# VDC.net
KiCad netlist of a schematic drawn in EAGLE
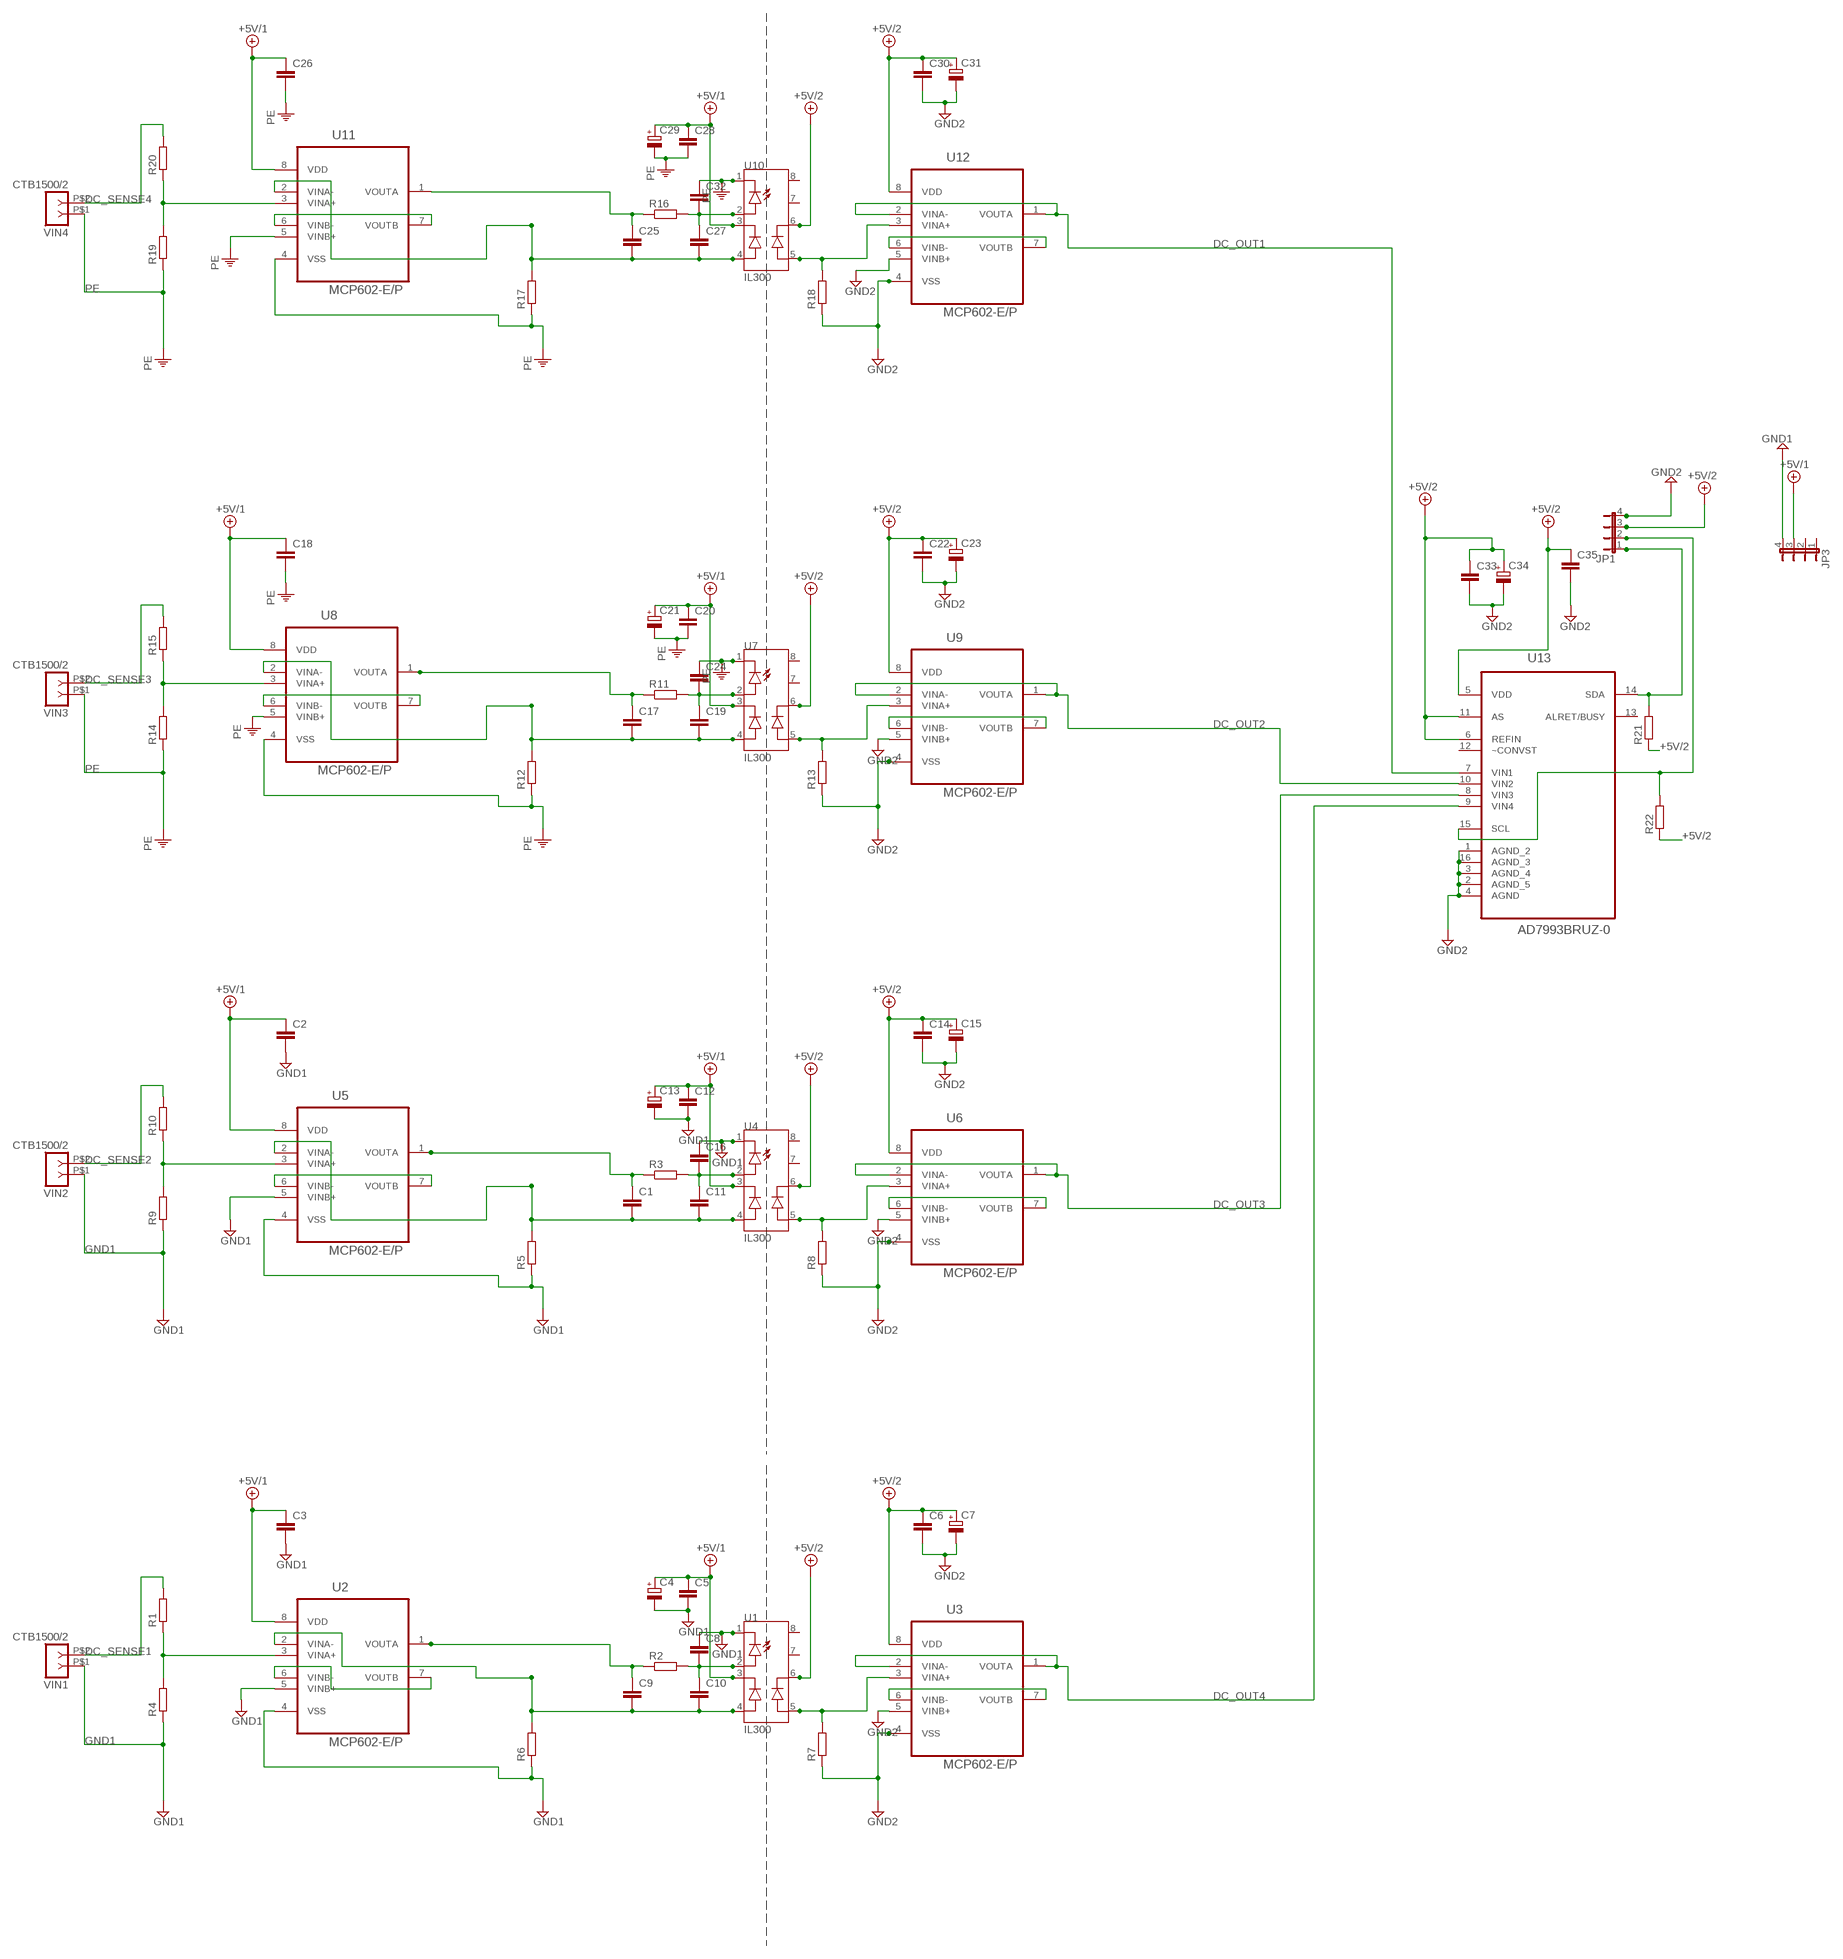
[diagram p0: schematic, sheet 1]

(export (version "E")
  (design (tool "Eeschema 10.0.6"))
  (components
    (comp (ref "C1")
      (value "C-EU025-040X050")
      (footprint "eagle-import:C025-040X050")
      (libsource (lib "eagle-import") (part "C-EU025-040X050"))
    )
    (comp (ref "C2")
      (value "C-EU025-040X050")
      (footprint "eagle-import:C025-040X050")
      (libsource (lib "eagle-import") (part "C-EU025-040X050"))
    )
    (comp (ref "C3")
      (value "C-EU025-040X050")
      (footprint "eagle-import:C025-040X050")
      (libsource (lib "eagle-import") (part "C-EU025-040X050"))
    )
    (comp (ref "C4")
      (value "CPOL-EUE2-5")
      (footprint "eagle-import:E2-5")
      (libsource (lib "eagle-import") (part "CPOL-EUE2-5"))
    )
    (comp (ref "C5")
      (value "C-EU025-040X050")
      (footprint "eagle-import:C025-040X050")
      (libsource (lib "eagle-import") (part "C-EU025-040X050"))
    )
    (comp (ref "C6")
      (value "C-EU025-040X050")
      (footprint "eagle-import:C025-040X050")
      (libsource (lib "eagle-import") (part "C-EU025-040X050"))
    )
    (comp (ref "C7")
      (value "CPOL-EUE2-5")
      (footprint "eagle-import:E2-5")
      (libsource (lib "eagle-import") (part "CPOL-EUE2-5"))
    )
    (comp (ref "C8")
      (value "C-EU025-040X050")
      (footprint "eagle-import:C025-040X050")
      (libsource (lib "eagle-import") (part "C-EU025-040X050"))
    )
    (comp (ref "C9")
      (value "C-EU025-040X050")
      (footprint "eagle-import:C025-040X050")
      (libsource (lib "eagle-import") (part "C-EU025-040X050"))
    )
    (comp (ref "C10")
      (value "C-EU025-040X050")
      (footprint "eagle-import:C025-040X050")
      (libsource (lib "eagle-import") (part "C-EU025-040X050"))
    )
    (comp (ref "C11")
      (value "C-EU025-040X050")
      (footprint "eagle-import:C025-040X050")
      (libsource (lib "eagle-import") (part "C-EU025-040X050"))
    )
    (comp (ref "C12")
      (value "C-EU025-040X050")
      (footprint "eagle-import:C025-040X050")
      (libsource (lib "eagle-import") (part "C-EU025-040X050"))
    )
    (comp (ref "C13")
      (value "CPOL-EUE2-5")
      (footprint "eagle-import:E2-5")
      (libsource (lib "eagle-import") (part "CPOL-EUE2-5"))
    )
    (comp (ref "C14")
      (value "C-EU025-040X050")
      (footprint "eagle-import:C025-040X050")
      (libsource (lib "eagle-import") (part "C-EU025-040X050"))
    )
    (comp (ref "C15")
      (value "CPOL-EUE2-5")
      (footprint "eagle-import:E2-5")
      (libsource (lib "eagle-import") (part "CPOL-EUE2-5"))
    )
    (comp (ref "C16")
      (value "C-EU025-040X050")
      (footprint "eagle-import:C025-040X050")
      (libsource (lib "eagle-import") (part "C-EU025-040X050"))
    )
    (comp (ref "C17")
      (value "C-EU025-040X050")
      (footprint "eagle-import:C025-040X050")
      (libsource (lib "eagle-import") (part "C-EU025-040X050"))
    )
    (comp (ref "C18")
      (value "C-EU025-040X050")
      (footprint "eagle-import:C025-040X050")
      (libsource (lib "eagle-import") (part "C-EU025-040X050"))
    )
    (comp (ref "C19")
      (value "C-EU025-040X050")
      (footprint "eagle-import:C025-040X050")
      (libsource (lib "eagle-import") (part "C-EU025-040X050"))
    )
    (comp (ref "C20")
      (value "C-EU025-040X050")
      (footprint "eagle-import:C025-040X050")
      (libsource (lib "eagle-import") (part "C-EU025-040X050"))
    )
    (comp (ref "C21")
      (value "CPOL-EUE2-5")
      (footprint "eagle-import:E2-5")
      (libsource (lib "eagle-import") (part "CPOL-EUE2-5"))
    )
    (comp (ref "C22")
      (value "C-EU025-040X050")
      (footprint "eagle-import:C025-040X050")
      (libsource (lib "eagle-import") (part "C-EU025-040X050"))
    )
    (comp (ref "C23")
      (value "CPOL-EUE2-5")
      (footprint "eagle-import:E2-5")
      (libsource (lib "eagle-import") (part "CPOL-EUE2-5"))
    )
    (comp (ref "C24")
      (value "C-EU025-040X050")
      (footprint "eagle-import:C025-040X050")
      (libsource (lib "eagle-import") (part "C-EU025-040X050"))
    )
    (comp (ref "C25")
      (value "C-EU025-040X050")
      (footprint "eagle-import:C025-040X050")
      (libsource (lib "eagle-import") (part "C-EU025-040X050"))
    )
    (comp (ref "C26")
      (value "C-EU025-040X050")
      (footprint "eagle-import:C025-040X050")
      (libsource (lib "eagle-import") (part "C-EU025-040X050"))
    )
    (comp (ref "C27")
      (value "C-EU025-040X050")
      (footprint "eagle-import:C025-040X050")
      (libsource (lib "eagle-import") (part "C-EU025-040X050"))
    )
    (comp (ref "C28")
      (value "C-EU025-040X050")
      (footprint "eagle-import:C025-040X050")
      (libsource (lib "eagle-import") (part "C-EU025-040X050"))
    )
    (comp (ref "C29")
      (value "CPOL-EUE2-5")
      (footprint "eagle-import:E2-5")
      (libsource (lib "eagle-import") (part "CPOL-EUE2-5"))
    )
    (comp (ref "C30")
      (value "C-EU025-040X050")
      (footprint "eagle-import:C025-040X050")
      (libsource (lib "eagle-import") (part "C-EU025-040X050"))
    )
    (comp (ref "C31")
      (value "CPOL-EUE2-5")
      (footprint "eagle-import:E2-5")
      (libsource (lib "eagle-import") (part "CPOL-EUE2-5"))
    )
    (comp (ref "C32")
      (value "C-EU025-040X050")
      (footprint "eagle-import:C025-040X050")
      (libsource (lib "eagle-import") (part "C-EU025-040X050"))
    )
    (comp (ref "C33")
      (value "C-EU025-024X044")
      (footprint "eagle-import:C025-024X044")
      (libsource (lib "eagle-import") (part "C-EU025-024X044"))
    )
    (comp (ref "C34")
      (value "CPOL-EUE2-4")
      (footprint "eagle-import:E2-4")
      (libsource (lib "eagle-import") (part "CPOL-EUE2-4"))
    )
    (comp (ref "C35")
      (value "C-EU025-025X050")
      (footprint "eagle-import:C025-025X050")
      (libsource (lib "eagle-import") (part "C-EU025-025X050"))
    )
    (comp (ref "JP1")
      (value "JP4E")
      (footprint "eagle-import:JP4")
      (libsource (lib "eagle-import") (part "JP4E"))
    )
    (comp (ref "JP3")
      (value "JP4E")
      (footprint "eagle-import:JP4")
      (libsource (lib "eagle-import") (part "JP4E"))
    )
    (comp (ref "R1")
      (value "R-EU_0207/10")
      (footprint "eagle-import:0207_10")
      (libsource (lib "eagle-import") (part "R-EU_0207/10"))
    )
    (comp (ref "R2")
      (value "R-EU_0207/10")
      (footprint "eagle-import:0207_10")
      (libsource (lib "eagle-import") (part "R-EU_0207/10"))
    )
    (comp (ref "R3")
      (value "R-EU_0207/10")
      (footprint "eagle-import:0207_10")
      (libsource (lib "eagle-import") (part "R-EU_0207/10"))
    )
    (comp (ref "R4")
      (value "R-EU_0207/10")
      (footprint "eagle-import:0207_10")
      (libsource (lib "eagle-import") (part "R-EU_0207/10"))
    )
    (comp (ref "R5")
      (value "R-EU_0207/10")
      (footprint "eagle-import:0207_10")
      (libsource (lib "eagle-import") (part "R-EU_0207/10"))
    )
    (comp (ref "R6")
      (value "R-EU_0207/10")
      (footprint "eagle-import:0207_10")
      (libsource (lib "eagle-import") (part "R-EU_0207/10"))
    )
    (comp (ref "R7")
      (value "R-EU_0207/10")
      (footprint "eagle-import:0207_10")
      (libsource (lib "eagle-import") (part "R-EU_0207/10"))
    )
    (comp (ref "R8")
      (value "R-EU_0207/10")
      (footprint "eagle-import:0207_10")
      (libsource (lib "eagle-import") (part "R-EU_0207/10"))
    )
    (comp (ref "R9")
      (value "R-EU_0207/10")
      (footprint "eagle-import:0207_10")
      (libsource (lib "eagle-import") (part "R-EU_0207/10"))
    )
    (comp (ref "R10")
      (value "R-EU_0207/10")
      (footprint "eagle-import:0207_10")
      (libsource (lib "eagle-import") (part "R-EU_0207/10"))
    )
    (comp (ref "R11")
      (value "R-EU_0207/10")
      (footprint "eagle-import:0207_10")
      (libsource (lib "eagle-import") (part "R-EU_0207/10"))
    )
    (comp (ref "R12")
      (value "R-EU_0207/10")
      (footprint "eagle-import:0207_10")
      (libsource (lib "eagle-import") (part "R-EU_0207/10"))
    )
    (comp (ref "R13")
      (value "R-EU_0207/10")
      (footprint "eagle-import:0207_10")
      (libsource (lib "eagle-import") (part "R-EU_0207/10"))
    )
    (comp (ref "R14")
      (value "R-EU_0207/10")
      (footprint "eagle-import:0207_10")
      (libsource (lib "eagle-import") (part "R-EU_0207/10"))
    )
    (comp (ref "R15")
      (value "R-EU_0207/10")
      (footprint "eagle-import:0207_10")
      (libsource (lib "eagle-import") (part "R-EU_0207/10"))
    )
    (comp (ref "R16")
      (value "R-EU_0207/10")
      (footprint "eagle-import:0207_10")
      (libsource (lib "eagle-import") (part "R-EU_0207/10"))
    )
    (comp (ref "R17")
      (value "R-EU_0207/10")
      (footprint "eagle-import:0207_10")
      (libsource (lib "eagle-import") (part "R-EU_0207/10"))
    )
    (comp (ref "R18")
      (value "R-EU_0207/10")
      (footprint "eagle-import:0207_10")
      (libsource (lib "eagle-import") (part "R-EU_0207/10"))
    )
    (comp (ref "R19")
      (value "R-EU_0207/10")
      (footprint "eagle-import:0207_10")
      (libsource (lib "eagle-import") (part "R-EU_0207/10"))
    )
    (comp (ref "R20")
      (value "R-EU_0207/10")
      (footprint "eagle-import:0207_10")
      (libsource (lib "eagle-import") (part "R-EU_0207/10"))
    )
    (comp (ref "R21")
      (value "R-EU_0207/10")
      (footprint "eagle-import:0207_10")
      (libsource (lib "eagle-import") (part "R-EU_0207/10"))
    )
    (comp (ref "R22")
      (value "R-EU_0207/10")
      (footprint "eagle-import:0207_10")
      (libsource (lib "eagle-import") (part "R-EU_0207/10"))
    )
    (comp (ref "U1")
      (value "IL300")
      (footprint "eagle-import:DIL08")
      (libsource (lib "eagle-import") (part "IL300"))
    )
    (comp (ref "U2")
      (value "MCP602-E/P")
      (footprint "eagle-import:DIP254P762X508-8P")
      (libsource (lib "eagle-import") (part "MCP602-E/P"))
    )
    (comp (ref "U3")
      (value "MCP602-E/P")
      (footprint "eagle-import:DIP254P762X508-8P")
      (libsource (lib "eagle-import") (part "MCP602-E/P"))
    )
    (comp (ref "U4")
      (value "IL300")
      (footprint "eagle-import:DIL08")
      (libsource (lib "eagle-import") (part "IL300"))
    )
    (comp (ref "U5")
      (value "MCP602-E/P")
      (footprint "eagle-import:DIP254P762X508-8P")
      (libsource (lib "eagle-import") (part "MCP602-E/P"))
    )
    (comp (ref "U6")
      (value "MCP602-E/P")
      (footprint "eagle-import:DIP254P762X508-8P")
      (libsource (lib "eagle-import") (part "MCP602-E/P"))
    )
    (comp (ref "U7")
      (value "IL300")
      (footprint "eagle-import:DIL08")
      (libsource (lib "eagle-import") (part "IL300"))
    )
    (comp (ref "U8")
      (value "MCP602-E/P")
      (footprint "eagle-import:DIP254P762X508-8P")
      (libsource (lib "eagle-import") (part "MCP602-E/P"))
    )
    (comp (ref "U9")
      (value "MCP602-E/P")
      (footprint "eagle-import:DIP254P762X508-8P")
      (libsource (lib "eagle-import") (part "MCP602-E/P"))
    )
    (comp (ref "U10")
      (value "IL300")
      (footprint "eagle-import:DIL08")
      (libsource (lib "eagle-import") (part "IL300"))
    )
    (comp (ref "U11")
      (value "MCP602-E/P")
      (footprint "eagle-import:DIP254P762X508-8P")
      (libsource (lib "eagle-import") (part "MCP602-E/P"))
    )
    (comp (ref "U12")
      (value "MCP602-E/P")
      (footprint "eagle-import:DIP254P762X508-8P")
      (libsource (lib "eagle-import") (part "MCP602-E/P"))
    )
    (comp (ref "U13")
      (value "AD7993BRUZ-0")
      (footprint "eagle-import:SOP65P640X120-16N")
      (libsource (lib "eagle-import") (part "AD7993BRUZ-0"))
    )
    (comp (ref "VIN1")
      (value "CTB1500/2")
      (footprint "eagle-import:CTB1500-2")
      (libsource (lib "eagle-import") (part "CTB1500/2"))
    )
    (comp (ref "VIN2")
      (value "CTB1500/2")
      (footprint "eagle-import:CTB1500-2")
      (libsource (lib "eagle-import") (part "CTB1500/2"))
    )
    (comp (ref "VIN3")
      (value "CTB1500/2")
      (footprint "eagle-import:CTB1500-2")
      (libsource (lib "eagle-import") (part "CTB1500/2"))
    )
    (comp (ref "VIN4")
      (value "CTB1500/2")
      (footprint "eagle-import:CTB1500-2")
      (libsource (lib "eagle-import") (part "CTB1500/2"))
    )
  )
  (nets
    (net (code "1") (name "+5V{slash}1") (class "Default")
      (node (ref "C12") (pin "1") (pinfunction "1_1") (pintype "passive"))
      (node (ref "C13") (pin "+") (pinfunction "+_+") (pintype "passive"))
      (node (ref "C18") (pin "1") (pinfunction "1_1") (pintype "passive"))
      (node (ref "C2") (pin "1") (pinfunction "1_1") (pintype "passive"))
      (node (ref "C20") (pin "1") (pinfunction "1_1") (pintype "passive"))
      (node (ref "C21") (pin "+") (pinfunction "+_+") (pintype "passive"))
      (node (ref "C26") (pin "1") (pinfunction "1_1") (pintype "passive"))
      (node (ref "C28") (pin "1") (pinfunction "1_1") (pintype "passive"))
      (node (ref "C29") (pin "+") (pinfunction "+_+") (pintype "passive"))
      (node (ref "C3") (pin "1") (pinfunction "1_1") (pintype "passive"))
      (node (ref "C4") (pin "+") (pinfunction "+_+") (pintype "passive"))
      (node (ref "C5") (pin "1") (pinfunction "1_1") (pintype "passive"))
      (node (ref "JP3") (pin "3") (pinfunction "3_3") (pintype "passive"))
      (node (ref "U1") (pin "3") (pinfunction "C_FB_3") (pintype "passive"))
      (node (ref "U10") (pin "3") (pinfunction "C_FB_3") (pintype "passive"))
      (node (ref "U11") (pin "8") (pinfunction "VDD_8") (pintype "power_in"))
      (node (ref "U2") (pin "8") (pinfunction "VDD_8") (pintype "power_in"))
      (node (ref "U4") (pin "3") (pinfunction "C_FB_3") (pintype "passive"))
      (node (ref "U5") (pin "8") (pinfunction "VDD_8") (pintype "power_in"))
      (node (ref "U7") (pin "3") (pinfunction "C_FB_3") (pintype "passive"))
      (node (ref "U8") (pin "8") (pinfunction "VDD_8") (pintype "power_in"))
    )
    (net (code "2") (name "+5V{slash}2") (class "Default")
      (node (ref "C14") (pin "1") (pinfunction "1_1") (pintype "passive"))
      (node (ref "C15") (pin "+") (pinfunction "+_+") (pintype "passive"))
      (node (ref "C22") (pin "1") (pinfunction "1_1") (pintype "passive"))
      (node (ref "C23") (pin "+") (pinfunction "+_+") (pintype "passive"))
      (node (ref "C30") (pin "1") (pinfunction "1_1") (pintype "passive"))
      (node (ref "C31") (pin "+") (pinfunction "+_+") (pintype "passive"))
      (node (ref "C33") (pin "1") (pinfunction "1_1") (pintype "passive"))
      (node (ref "C34") (pin "+") (pinfunction "+_+") (pintype "passive"))
      (node (ref "C35") (pin "1") (pinfunction "1_1") (pintype "passive"))
      (node (ref "C6") (pin "1") (pinfunction "1_1") (pintype "passive"))
      (node (ref "C7") (pin "+") (pinfunction "+_+") (pintype "passive"))
      (node (ref "JP1") (pin "3") (pinfunction "3_3") (pintype "passive"))
      (node (ref "R21") (pin "1") (pinfunction "1_1") (pintype "passive"))
      (node (ref "R22") (pin "1") (pinfunction "1_1") (pintype "passive"))
      (node (ref "U1") (pin "6") (pinfunction "C_OUT_6") (pintype "passive"))
      (node (ref "U10") (pin "6") (pinfunction "C_OUT_6") (pintype "passive"))
      (node (ref "U12") (pin "8") (pinfunction "VDD_8") (pintype "power_in"))
      (node (ref "U13") (pin "11") (pinfunction "AS_11") (pintype "input"))
      (node (ref "U13") (pin "5") (pinfunction "VDD_5") (pintype "power_in"))
      (node (ref "U13") (pin "6") (pinfunction "REFIN_6") (pintype "input"))
      (node (ref "U3") (pin "8") (pinfunction "VDD_8") (pintype "power_in"))
      (node (ref "U4") (pin "6") (pinfunction "C_OUT_6") (pintype "passive"))
      (node (ref "U6") (pin "8") (pinfunction "VDD_8") (pintype "power_in"))
      (node (ref "U7") (pin "6") (pinfunction "C_OUT_6") (pintype "passive"))
      (node (ref "U9") (pin "8") (pinfunction "VDD_8") (pintype "power_in"))
    )
    (net (code "3") (name "/DC_OUT1") (class "Default")
      (node (ref "U12") (pin "1") (pinfunction "VOUTA_1") (pintype "output"))
      (node (ref "U12") (pin "2") (pinfunction "VINA-_2") (pintype "input"))
      (node (ref "U13") (pin "7") (pinfunction "VIN1_7") (pintype "input"))
    )
    (net (code "4") (name "/DC_OUT2") (class "Default")
      (node (ref "U13") (pin "10") (pinfunction "VIN2_10") (pintype "input"))
      (node (ref "U9") (pin "1") (pinfunction "VOUTA_1") (pintype "output"))
      (node (ref "U9") (pin "2") (pinfunction "VINA-_2") (pintype "input"))
    )
    (net (code "5") (name "/DC_OUT3") (class "Default")
      (node (ref "U13") (pin "8") (pinfunction "VIN3_8") (pintype "input"))
      (node (ref "U6") (pin "1") (pinfunction "VOUTA_1") (pintype "output"))
      (node (ref "U6") (pin "2") (pinfunction "VINA-_2") (pintype "input"))
    )
    (net (code "6") (name "/DC_OUT4") (class "Default")
      (node (ref "U13") (pin "9") (pinfunction "VIN4_9") (pintype "input"))
      (node (ref "U3") (pin "1") (pinfunction "VOUTA_1") (pintype "output"))
      (node (ref "U3") (pin "2") (pinfunction "VINA-_2") (pintype "input"))
    )
    (net (code "7") (name "/DC_SENSE1") (class "Default")
      (node (ref "R1") (pin "2") (pinfunction "2_2") (pintype "passive"))
      (node (ref "VIN1") (pin "P$2") (pinfunction "2_P$2") (pintype "passive"))
    )
    (net (code "8") (name "/DC_SENSE2") (class "Default")
      (node (ref "R10") (pin "2") (pinfunction "2_2") (pintype "passive"))
      (node (ref "VIN2") (pin "P$2") (pinfunction "2_P$2") (pintype "passive"))
    )
    (net (code "9") (name "/DC_SENSE3") (class "Default")
      (node (ref "R15") (pin "2") (pinfunction "2_2") (pintype "passive"))
      (node (ref "VIN3") (pin "P$2") (pinfunction "2_P$2") (pintype "passive"))
    )
    (net (code "10") (name "/DC_SENSE4") (class "Default")
      (node (ref "R20") (pin "2") (pinfunction "2_2") (pintype "passive"))
      (node (ref "VIN4") (pin "P$2") (pinfunction "2_P$2") (pintype "passive"))
    )
    (net (code "11") (name "GND1") (class "Default")
      (node (ref "C12") (pin "2") (pinfunction "2_2") (pintype "passive"))
      (node (ref "C13") (pin "-") (pinfunction "-_-") (pintype "passive"))
      (node (ref "C16") (pin "1") (pinfunction "1_1") (pintype "passive"))
      (node (ref "C2") (pin "2") (pinfunction "2_2") (pintype "passive"))
      (node (ref "C3") (pin "2") (pinfunction "2_2") (pintype "passive"))
      (node (ref "C4") (pin "-") (pinfunction "-_-") (pintype "passive"))
      (node (ref "C5") (pin "2") (pinfunction "2_2") (pintype "passive"))
      (node (ref "C8") (pin "1") (pinfunction "1_1") (pintype "passive"))
      (node (ref "JP3") (pin "4") (pinfunction "4_4") (pintype "passive"))
      (node (ref "R4") (pin "1") (pinfunction "1_1") (pintype "passive"))
      (node (ref "R5") (pin "1") (pinfunction "1_1") (pintype "passive"))
      (node (ref "R6") (pin "1") (pinfunction "1_1") (pintype "passive"))
      (node (ref "R9") (pin "1") (pinfunction "1_1") (pintype "passive"))
      (node (ref "U1") (pin "1") (pinfunction "C_LED_1") (pintype "passive"))
      (node (ref "U2") (pin "4") (pinfunction "VSS_4") (pintype "power_in"))
      (node (ref "U2") (pin "5") (pinfunction "VINB+_5") (pintype "input"))
      (node (ref "U4") (pin "1") (pinfunction "C_LED_1") (pintype "passive"))
      (node (ref "U5") (pin "4") (pinfunction "VSS_4") (pintype "power_in"))
      (node (ref "U5") (pin "5") (pinfunction "VINB+_5") (pintype "input"))
      (node (ref "VIN1") (pin "P$1") (pinfunction "1_P$1") (pintype "passive"))
      (node (ref "VIN2") (pin "P$1") (pinfunction "1_P$1") (pintype "passive"))
    )
    (net (code "12") (name "GND2") (class "Default")
      (node (ref "C14") (pin "2") (pinfunction "2_2") (pintype "passive"))
      (node (ref "C15") (pin "-") (pinfunction "-_-") (pintype "passive"))
      (node (ref "C22") (pin "2") (pinfunction "2_2") (pintype "passive"))
      (node (ref "C23") (pin "-") (pinfunction "-_-") (pintype "passive"))
      (node (ref "C30") (pin "2") (pinfunction "2_2") (pintype "passive"))
      (node (ref "C31") (pin "-") (pinfunction "-_-") (pintype "passive"))
      (node (ref "C33") (pin "2") (pinfunction "2_2") (pintype "passive"))
      (node (ref "C34") (pin "-") (pinfunction "-_-") (pintype "passive"))
      (node (ref "C35") (pin "2") (pinfunction "2_2") (pintype "passive"))
      (node (ref "C6") (pin "2") (pinfunction "2_2") (pintype "passive"))
      (node (ref "C7") (pin "-") (pinfunction "-_-") (pintype "passive"))
      (node (ref "JP1") (pin "4") (pinfunction "4_4") (pintype "passive"))
      (node (ref "R13") (pin "1") (pinfunction "1_1") (pintype "passive"))
      (node (ref "R18") (pin "1") (pinfunction "1_1") (pintype "passive"))
      (node (ref "R7") (pin "1") (pinfunction "1_1") (pintype "passive"))
      (node (ref "R8") (pin "1") (pinfunction "1_1") (pintype "passive"))
      (node (ref "U12") (pin "4") (pinfunction "VSS_4") (pintype "power_in"))
      (node (ref "U12") (pin "5") (pinfunction "VINB+_5") (pintype "input"))
      (node (ref "U13") (pin "1") (pinfunction "AGND_2_1") (pintype "passive"))
      (node (ref "U13") (pin "16") (pinfunction "AGND_3_16") (pintype "passive"))
      (node (ref "U13") (pin "2") (pinfunction "AGND_5_2") (pintype "passive"))
      (node (ref "U13") (pin "3") (pinfunction "AGND_4_3") (pintype "passive"))
      (node (ref "U13") (pin "4") (pinfunction "AGND_4") (pintype "passive"))
      (node (ref "U3") (pin "4") (pinfunction "VSS_4") (pintype "power_in"))
      (node (ref "U3") (pin "5") (pinfunction "VINB+_5") (pintype "input"))
      (node (ref "U6") (pin "4") (pinfunction "VSS_4") (pintype "power_in"))
      (node (ref "U6") (pin "5") (pinfunction "VINB+_5") (pintype "input"))
      (node (ref "U9") (pin "4") (pinfunction "VSS_4") (pintype "power_in"))
      (node (ref "U9") (pin "5") (pinfunction "VINB+_5") (pintype "input"))
    )
    (net (code "13") (name "Net-(U1-A_FB)") (class "Default")
      (node (ref "C10") (pin "2") (pinfunction "2_2") (pintype "passive"))
      (node (ref "C9") (pin "2") (pinfunction "2_2") (pintype "passive"))
      (node (ref "R6") (pin "2") (pinfunction "2_2") (pintype "passive"))
      (node (ref "U1") (pin "4") (pinfunction "A_FB_4") (pintype "passive"))
      (node (ref "U2") (pin "2") (pinfunction "VINA-_2") (pintype "input"))
    )
    (net (code "14") (name "Net-(U1-A_LED)") (class "Default")
      (node (ref "C10") (pin "1") (pinfunction "1_1") (pintype "passive"))
      (node (ref "C8") (pin "2") (pinfunction "2_2") (pintype "passive"))
      (node (ref "R2") (pin "2") (pinfunction "2_2") (pintype "passive"))
      (node (ref "U1") (pin "2") (pinfunction "A_LED_2") (pintype "passive"))
    )
    (net (code "15") (name "Net-(U1-A_OUT)") (class "Default")
      (node (ref "R7") (pin "2") (pinfunction "2_2") (pintype "passive"))
      (node (ref "U1") (pin "5") (pinfunction "A_OUT_5") (pintype "passive"))
      (node (ref "U3") (pin "3") (pinfunction "VINA+_3") (pintype "input"))
    )
    (net (code "16") (name "Net-(U2-VINA+)") (class "Default")
      (node (ref "R1") (pin "1") (pinfunction "1_1") (pintype "passive"))
      (node (ref "R4") (pin "2") (pinfunction "2_2") (pintype "passive"))
      (node (ref "U2") (pin "3") (pinfunction "VINA+_3") (pintype "input"))
    )
    (net (code "17") (name "Net-(U2-VINB-)") (class "Default")
      (node (ref "U2") (pin "6") (pinfunction "VINB-_6") (pintype "input"))
      (node (ref "U2") (pin "7") (pinfunction "VOUTB_7") (pintype "output"))
    )
    (net (code "18") (name "Net-(U2-VOUTA)") (class "Default")
      (node (ref "C9") (pin "1") (pinfunction "1_1") (pintype "passive"))
      (node (ref "R2") (pin "1") (pinfunction "1_1") (pintype "passive"))
      (node (ref "U2") (pin "1") (pinfunction "VOUTA_1") (pintype "output"))
    )
    (net (code "19") (name "Net-(U3-VINB-)") (class "Default")
      (node (ref "U3") (pin "6") (pinfunction "VINB-_6") (pintype "input"))
      (node (ref "U3") (pin "7") (pinfunction "VOUTB_7") (pintype "output"))
    )
    (net (code "20") (name "Net-(U4-A_FB)") (class "Default")
      (node (ref "C1") (pin "2") (pinfunction "2_2") (pintype "passive"))
      (node (ref "C11") (pin "2") (pinfunction "2_2") (pintype "passive"))
      (node (ref "R5") (pin "2") (pinfunction "2_2") (pintype "passive"))
      (node (ref "U4") (pin "4") (pinfunction "A_FB_4") (pintype "passive"))
      (node (ref "U5") (pin "2") (pinfunction "VINA-_2") (pintype "input"))
    )
    (net (code "21") (name "Net-(U4-A_LED)") (class "Default")
      (node (ref "C11") (pin "1") (pinfunction "1_1") (pintype "passive"))
      (node (ref "C16") (pin "2") (pinfunction "2_2") (pintype "passive"))
      (node (ref "R3") (pin "2") (pinfunction "2_2") (pintype "passive"))
      (node (ref "U4") (pin "2") (pinfunction "A_LED_2") (pintype "passive"))
    )
    (net (code "22") (name "Net-(U4-A_OUT)") (class "Default")
      (node (ref "R8") (pin "2") (pinfunction "2_2") (pintype "passive"))
      (node (ref "U4") (pin "5") (pinfunction "A_OUT_5") (pintype "passive"))
      (node (ref "U6") (pin "3") (pinfunction "VINA+_3") (pintype "input"))
    )
    (net (code "23") (name "Net-(U5-VINA+)") (class "Default")
      (node (ref "R10") (pin "1") (pinfunction "1_1") (pintype "passive"))
      (node (ref "R9") (pin "2") (pinfunction "2_2") (pintype "passive"))
      (node (ref "U5") (pin "3") (pinfunction "VINA+_3") (pintype "input"))
    )
    (net (code "24") (name "Net-(U5-VINB-)") (class "Default")
      (node (ref "U5") (pin "6") (pinfunction "VINB-_6") (pintype "input"))
      (node (ref "U5") (pin "7") (pinfunction "VOUTB_7") (pintype "output"))
    )
    (net (code "25") (name "Net-(U5-VOUTA)") (class "Default")
      (node (ref "C1") (pin "1") (pinfunction "1_1") (pintype "passive"))
      (node (ref "R3") (pin "1") (pinfunction "1_1") (pintype "passive"))
      (node (ref "U5") (pin "1") (pinfunction "VOUTA_1") (pintype "output"))
    )
    (net (code "26") (name "Net-(U6-VINB-)") (class "Default")
      (node (ref "U6") (pin "6") (pinfunction "VINB-_6") (pintype "input"))
      (node (ref "U6") (pin "7") (pinfunction "VOUTB_7") (pintype "output"))
    )
    (net (code "27") (name "Net-(U7-A_FB)") (class "Default")
      (node (ref "C17") (pin "2") (pinfunction "2_2") (pintype "passive"))
      (node (ref "C19") (pin "2") (pinfunction "2_2") (pintype "passive"))
      (node (ref "R12") (pin "2") (pinfunction "2_2") (pintype "passive"))
      (node (ref "U7") (pin "4") (pinfunction "A_FB_4") (pintype "passive"))
      (node (ref "U8") (pin "2") (pinfunction "VINA-_2") (pintype "input"))
    )
    (net (code "28") (name "Net-(U7-A_LED)") (class "Default")
      (node (ref "C19") (pin "1") (pinfunction "1_1") (pintype "passive"))
      (node (ref "C24") (pin "2") (pinfunction "2_2") (pintype "passive"))
      (node (ref "R11") (pin "2") (pinfunction "2_2") (pintype "passive"))
      (node (ref "U7") (pin "2") (pinfunction "A_LED_2") (pintype "passive"))
    )
    (net (code "29") (name "Net-(U7-A_OUT)") (class "Default")
      (node (ref "R13") (pin "2") (pinfunction "2_2") (pintype "passive"))
      (node (ref "U7") (pin "5") (pinfunction "A_OUT_5") (pintype "passive"))
      (node (ref "U9") (pin "3") (pinfunction "VINA+_3") (pintype "input"))
    )
    (net (code "30") (name "Net-(U8-VINA+)") (class "Default")
      (node (ref "R14") (pin "2") (pinfunction "2_2") (pintype "passive"))
      (node (ref "R15") (pin "1") (pinfunction "1_1") (pintype "passive"))
      (node (ref "U8") (pin "3") (pinfunction "VINA+_3") (pintype "input"))
    )
    (net (code "31") (name "Net-(U8-VINB-)") (class "Default")
      (node (ref "U8") (pin "6") (pinfunction "VINB-_6") (pintype "input"))
      (node (ref "U8") (pin "7") (pinfunction "VOUTB_7") (pintype "output"))
    )
    (net (code "32") (name "Net-(U8-VOUTA)") (class "Default")
      (node (ref "C17") (pin "1") (pinfunction "1_1") (pintype "passive"))
      (node (ref "R11") (pin "1") (pinfunction "1_1") (pintype "passive"))
      (node (ref "U8") (pin "1") (pinfunction "VOUTA_1") (pintype "output"))
    )
    (net (code "33") (name "Net-(U9-VINB-)") (class "Default")
      (node (ref "U9") (pin "6") (pinfunction "VINB-_6") (pintype "input"))
      (node (ref "U9") (pin "7") (pinfunction "VOUTB_7") (pintype "output"))
    )
    (net (code "34") (name "Net-(U10-A_FB)") (class "Default")
      (node (ref "C25") (pin "2") (pinfunction "2_2") (pintype "passive"))
      (node (ref "C27") (pin "2") (pinfunction "2_2") (pintype "passive"))
      (node (ref "R17") (pin "2") (pinfunction "2_2") (pintype "passive"))
      (node (ref "U10") (pin "4") (pinfunction "A_FB_4") (pintype "passive"))
      (node (ref "U11") (pin "2") (pinfunction "VINA-_2") (pintype "input"))
    )
    (net (code "35") (name "Net-(U10-A_LED)") (class "Default")
      (node (ref "C27") (pin "1") (pinfunction "1_1") (pintype "passive"))
      (node (ref "C32") (pin "2") (pinfunction "2_2") (pintype "passive"))
      (node (ref "R16") (pin "2") (pinfunction "2_2") (pintype "passive"))
      (node (ref "U10") (pin "2") (pinfunction "A_LED_2") (pintype "passive"))
    )
    (net (code "36") (name "Net-(U10-A_OUT)") (class "Default")
      (node (ref "R18") (pin "2") (pinfunction "2_2") (pintype "passive"))
      (node (ref "U10") (pin "5") (pinfunction "A_OUT_5") (pintype "passive"))
      (node (ref "U12") (pin "3") (pinfunction "VINA+_3") (pintype "input"))
    )
    (net (code "37") (name "Net-(U11-VINA+)") (class "Default")
      (node (ref "R19") (pin "2") (pinfunction "2_2") (pintype "passive"))
      (node (ref "R20") (pin "1") (pinfunction "1_1") (pintype "passive"))
      (node (ref "U11") (pin "3") (pinfunction "VINA+_3") (pintype "input"))
    )
    (net (code "38") (name "Net-(U11-VINB-)") (class "Default")
      (node (ref "U11") (pin "6") (pinfunction "VINB-_6") (pintype "input"))
      (node (ref "U11") (pin "7") (pinfunction "VOUTB_7") (pintype "output"))
    )
    (net (code "39") (name "Net-(U11-VOUTA)") (class "Default")
      (node (ref "C25") (pin "1") (pinfunction "1_1") (pintype "passive"))
      (node (ref "R16") (pin "1") (pinfunction "1_1") (pintype "passive"))
      (node (ref "U11") (pin "1") (pinfunction "VOUTA_1") (pintype "output"))
    )
    (net (code "40") (name "Net-(U12-VINB-)") (class "Default")
      (node (ref "U12") (pin "6") (pinfunction "VINB-_6") (pintype "input"))
      (node (ref "U12") (pin "7") (pinfunction "VOUTB_7") (pintype "output"))
    )
    (net (code "41") (name "Net-(U13-SCL)") (class "Default")
      (node (ref "JP1") (pin "2") (pinfunction "2_2") (pintype "passive"))
      (node (ref "R22") (pin "2") (pinfunction "2_2") (pintype "passive"))
      (node (ref "U13") (pin "15") (pinfunction "SCL_15") (pintype "input"))
    )
    (net (code "42") (name "Net-(U13-SDA)") (class "Default")
      (node (ref "JP1") (pin "1") (pinfunction "1_1") (pintype "passive"))
      (node (ref "R21") (pin "2") (pinfunction "2_2") (pintype "passive"))
      (node (ref "U13") (pin "14") (pinfunction "SDA_14") (pintype "bidirectional"))
    )
    (net (code "43") (name "PE") (class "Default")
      (node (ref "C18") (pin "2") (pinfunction "2_2") (pintype "passive"))
      (node (ref "C20") (pin "2") (pinfunction "2_2") (pintype "passive"))
      (node (ref "C21") (pin "-") (pinfunction "-_-") (pintype "passive"))
      (node (ref "C24") (pin "1") (pinfunction "1_1") (pintype "passive"))
      (node (ref "C26") (pin "2") (pinfunction "2_2") (pintype "passive"))
      (node (ref "C28") (pin "2") (pinfunction "2_2") (pintype "passive"))
      (node (ref "C29") (pin "-") (pinfunction "-_-") (pintype "passive"))
      (node (ref "C32") (pin "1") (pinfunction "1_1") (pintype "passive"))
      (node (ref "R12") (pin "1") (pinfunction "1_1") (pintype "passive"))
      (node (ref "R14") (pin "1") (pinfunction "1_1") (pintype "passive"))
      (node (ref "R17") (pin "1") (pinfunction "1_1") (pintype "passive"))
      (node (ref "R19") (pin "1") (pinfunction "1_1") (pintype "passive"))
      (node (ref "U10") (pin "1") (pinfunction "C_LED_1") (pintype "passive"))
      (node (ref "U11") (pin "4") (pinfunction "VSS_4") (pintype "power_in"))
      (node (ref "U11") (pin "5") (pinfunction "VINB+_5") (pintype "input"))
      (node (ref "U7") (pin "1") (pinfunction "C_LED_1") (pintype "passive"))
      (node (ref "U8") (pin "4") (pinfunction "VSS_4") (pintype "power_in"))
      (node (ref "U8") (pin "5") (pinfunction "VINB+_5") (pintype "input"))
      (node (ref "VIN3") (pin "P$1") (pinfunction "1_P$1") (pintype "passive"))
      (node (ref "VIN4") (pin "P$1") (pinfunction "1_P$1") (pintype "passive"))
    )
    (net (code "44") (name "unconnected-(JP3-Pad1)") (class "Default")
      (node (ref "JP3") (pin "1") (pinfunction "1_1") (pintype "passive"))
    )
    (net (code "45") (name "unconnected-(JP3-Pad2)") (class "Default")
      (node (ref "JP3") (pin "2") (pinfunction "2_2") (pintype "passive"))
    )
    (net (code "46") (name "unconnected-(U1-PIN7-Pad7)") (class "Default")
      (node (ref "U1") (pin "7") (pinfunction "PIN7_7") (pintype "no_connect"))
    )
    (net (code "47") (name "unconnected-(U1-PIN8-Pad8)") (class "Default")
      (node (ref "U1") (pin "8") (pinfunction "PIN8_8") (pintype "no_connect"))
    )
    (net (code "48") (name "unconnected-(U4-PIN7-Pad7)") (class "Default")
      (node (ref "U4") (pin "7") (pinfunction "PIN7_7") (pintype "no_connect"))
    )
    (net (code "49") (name "unconnected-(U4-PIN8-Pad8)") (class "Default")
      (node (ref "U4") (pin "8") (pinfunction "PIN8_8") (pintype "no_connect"))
    )
    (net (code "50") (name "unconnected-(U7-PIN7-Pad7)") (class "Default")
      (node (ref "U7") (pin "7") (pinfunction "PIN7_7") (pintype "no_connect"))
    )
    (net (code "51") (name "unconnected-(U7-PIN8-Pad8)") (class "Default")
      (node (ref "U7") (pin "8") (pinfunction "PIN8_8") (pintype "no_connect"))
    )
    (net (code "52") (name "unconnected-(U10-PIN7-Pad7)") (class "Default")
      (node (ref "U10") (pin "7") (pinfunction "PIN7_7") (pintype "no_connect"))
    )
    (net (code "53") (name "unconnected-(U10-PIN8-Pad8)") (class "Default")
      (node (ref "U10") (pin "8") (pinfunction "PIN8_8") (pintype "no_connect"))
    )
    (net (code "54") (name "unconnected-(U13-ALRET{slash}BUSY-Pad13)") (class "Default")
      (node (ref "U13") (pin "13") (pinfunction "ALRET/BUSY_13") (pintype "output"))
    )
    (net (code "55") (name "unconnected-(U13-~{CONVST}-Pad12)") (class "Default")
      (node (ref "U13") (pin "12") (pinfunction "~{CONVST}_12") (pintype "input"))
    )
  )
)
